# ESP8266_Encoder.net
KiCad netlist of a schematic drawn in EAGLE
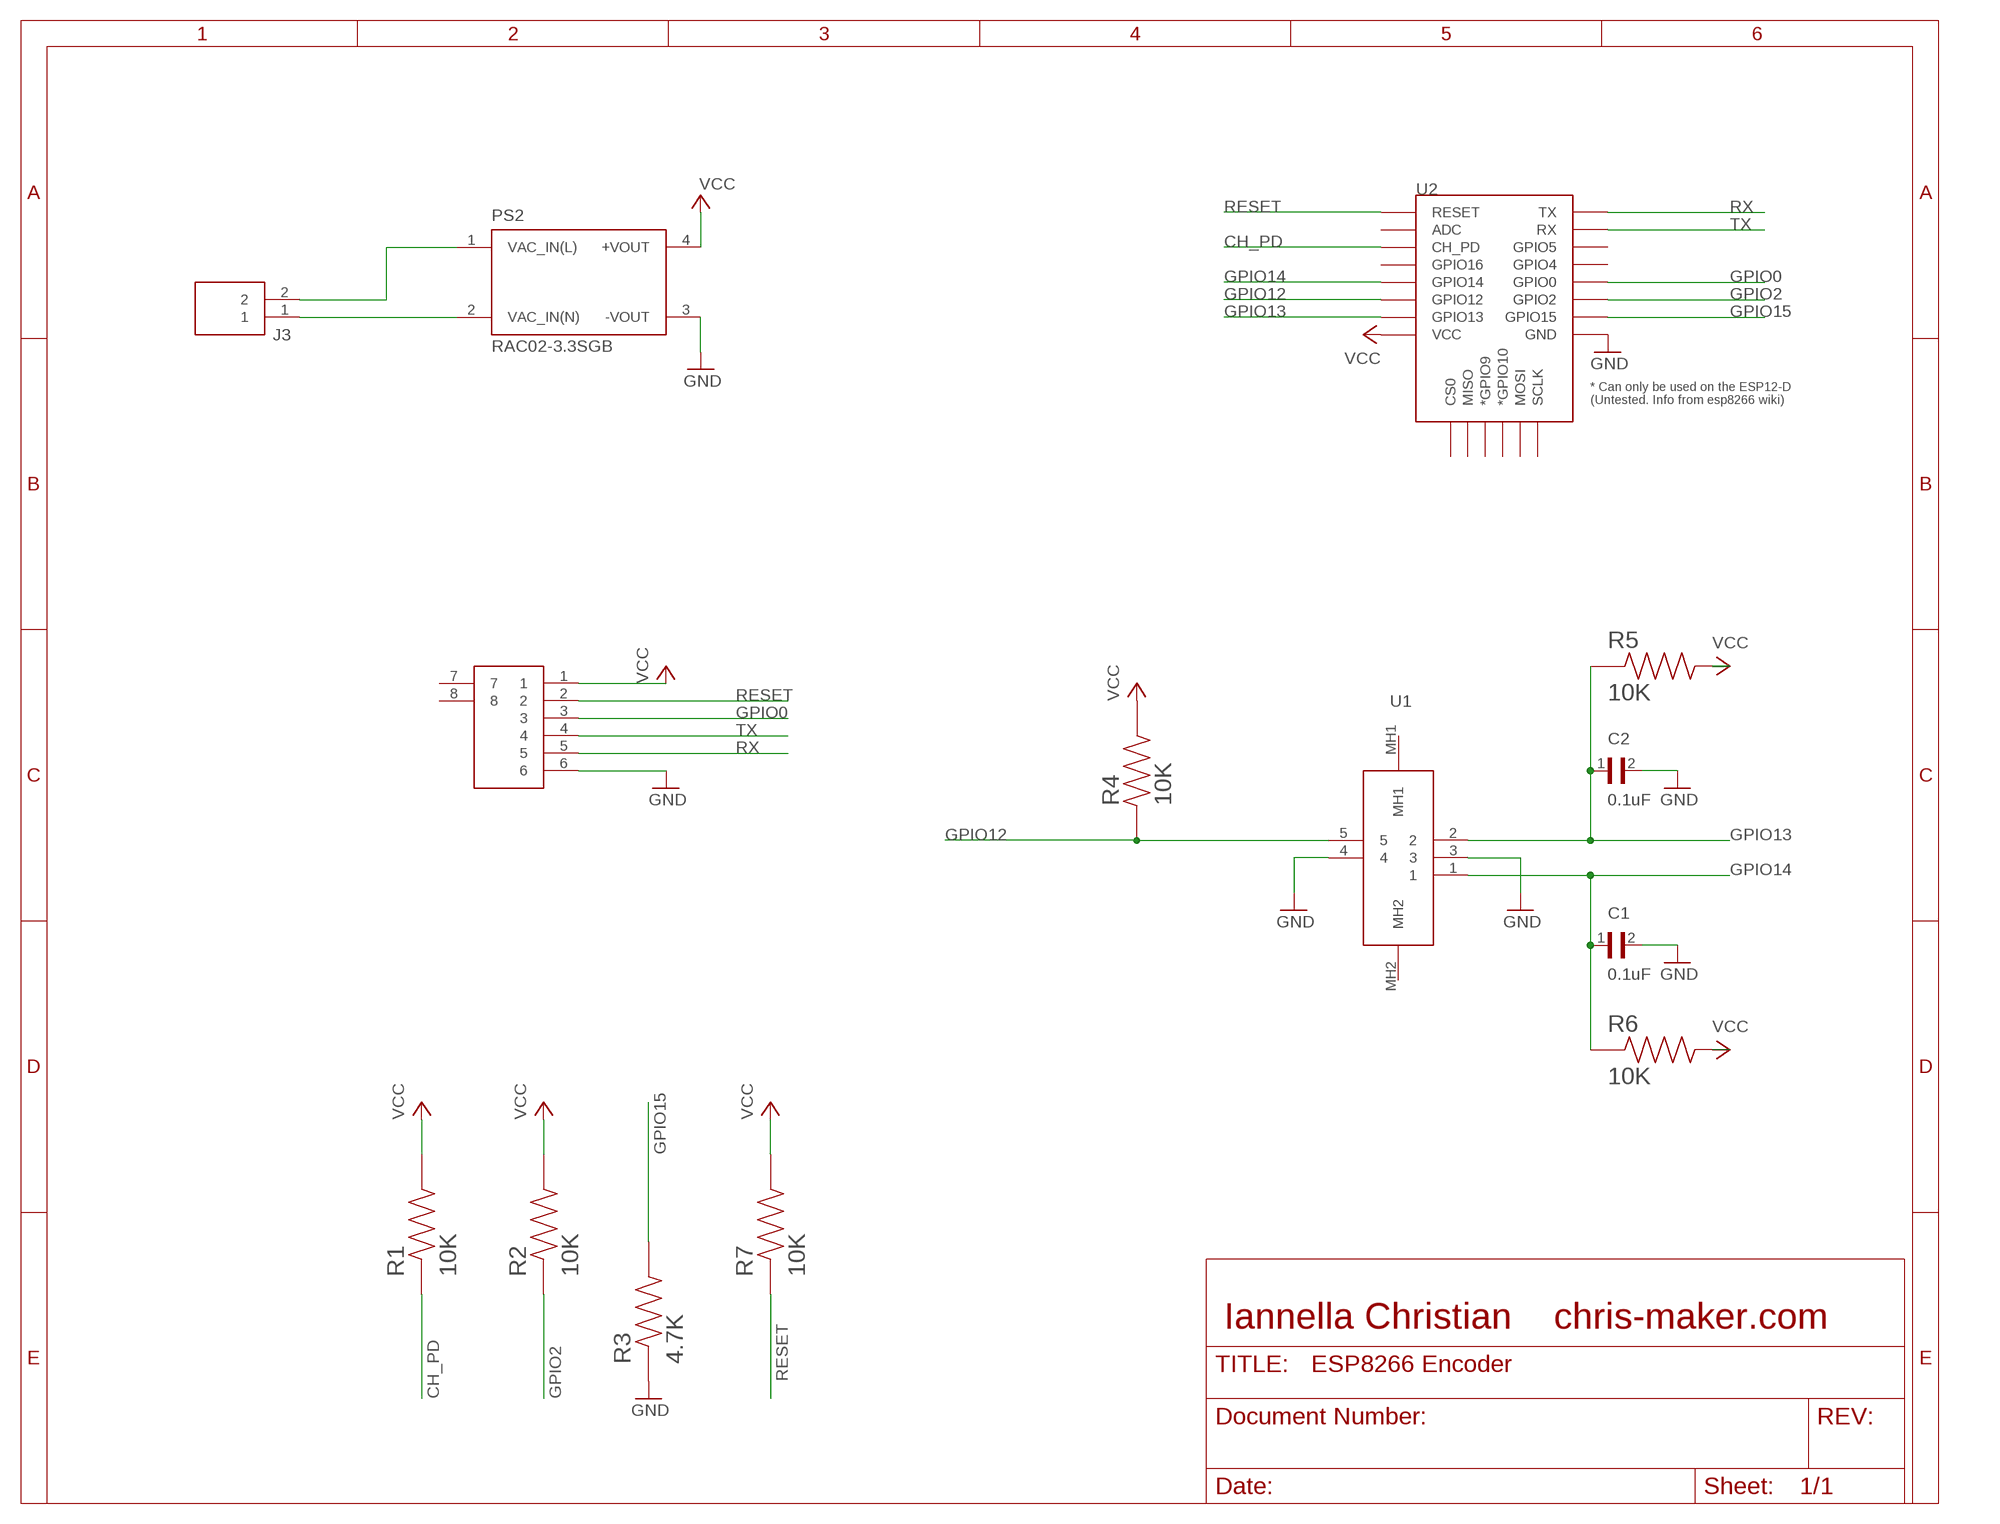
[diagram p0: schematic, sheet 1]

(export (version "E")
  (design (tool "Eeschema 10.0.6"))
  (components
    (comp (ref "C1")
      (value "0.1uF")
      (footprint "eagle-import:CAPC2012X94N")
      (fields (field (name "MF") "AVX") (field (name "MP") "0805YC103J4T2A"))
      (libsource (lib "eagle-import") (part "0805YC103J4T2A"))
    )
    (comp (ref "C2")
      (value "0.1uF")
      (footprint "eagle-import:CAPC2012X94N")
      (fields (field (name "MF") "AVX") (field (name "MP") "0805YC103J4T2A"))
      (libsource (lib "eagle-import") (part "0805YC103J4T2A"))
    )
    (comp (ref "J1")
      (value "52852-0670")
      (footprint "eagle-import:528520670")
      (fields (field (name "MOUSER_PART_NUMBER") "538-52852-0670"))
      (libsource (lib "eagle-import") (part "52852-0670"))
    )
    (comp (ref "J3")
      (value "TB004-508-02BE")
      (footprint "eagle-import:SHDR2W100P0X508_1X2_1016X1020X")
      (fields (field (name "MOUSER_PART_NUMBER") "490-TB004-508-02BE"))
      (libsource (lib "eagle-import") (part "TB004-508-02BE"))
    )
    (comp (ref "PS2")
      (value "RAC02-3.3SGB")
      (footprint "eagle-import:CONV_RAC02-3.3SGB")
      (fields (field (name "MF") "Recom Power"))
      (libsource (lib "eagle-import") (part "RAC02-3.3SGB"))
    )
    (comp (ref "R1")
      (value "10K")
      (footprint "eagle-import:RESC2012X60N")
      (fields (field (name "MF") "Yageo") (field (name "MP") "RC0805FR-07330RL"))
      (libsource (lib "eagle-import") (part "RC0805FR-07330RL"))
    )
    (comp (ref "R2")
      (value "10K")
      (footprint "eagle-import:RESC2012X60N")
      (fields (field (name "MF") "Yageo") (field (name "MP") "RC0805FR-07330RL"))
      (libsource (lib "eagle-import") (part "RC0805FR-07330RL"))
    )
    (comp (ref "R3")
      (value "4.7K")
      (footprint "eagle-import:RESC2012X60N")
      (fields (field (name "MF") "Yageo") (field (name "MP") "RC0805FR-07330RL"))
      (libsource (lib "eagle-import") (part "RC0805FR-07330RL"))
    )
    (comp (ref "R4")
      (value "10K")
      (footprint "eagle-import:RESC2012X60N")
      (fields (field (name "MF") "Yageo") (field (name "MP") "RC0805FR-07330RL"))
      (libsource (lib "eagle-import") (part "RC0805FR-07330RL"))
    )
    (comp (ref "R5")
      (value "10K")
      (footprint "eagle-import:RESC2012X60N")
      (fields (field (name "MF") "Yageo") (field (name "MP") "RC0805FR-07330RL"))
      (libsource (lib "eagle-import") (part "RC0805FR-07330RL"))
    )
    (comp (ref "R6")
      (value "10K")
      (footprint "eagle-import:RESC2012X60N")
      (fields (field (name "MF") "Yageo") (field (name "MP") "RC0805FR-07330RL"))
      (libsource (lib "eagle-import") (part "RC0805FR-07330RL"))
    )
    (comp (ref "R7")
      (value "10K")
      (footprint "eagle-import:RESC2012X60N")
      (fields (field (name "MF") "Yageo") (field (name "MP") "RC0805FR-07330RL"))
      (libsource (lib "eagle-import") (part "RC0805FR-07330RL"))
    )
    (comp (ref "U1")
      (value "ENCODER90")
      (footprint "eagle-import:EN11VSM0AF20")
      (fields (field (name "MANUFACTURER_PART_NUMBER") "EN11-VSM0AF20"))
      (libsource (lib "eagle-import") (part "ENCODER90"))
    )
    (comp (ref "U2")
      (value "ESP12ESMD")
      (footprint "eagle-import:ESP12E-SMD")
      (libsource (lib "eagle-import") (part "ESP12ESMD"))
    )
  )
  (nets
    (net (code "1") (name "/CH_PD") (class "Default")
      (node (ref "R1") (pin "1") (pinfunction "1_1") (pintype "passive"))
      (node (ref "U2") (pin "CH_PD") (pinfunction "CH_PD_CH_PD") (pintype "bidirectional"))
    )
    (net (code "2") (name "/GPIO0") (class "Default")
      (node (ref "J1") (pin "3") (pinfunction "3_3") (pintype "bidirectional"))
      (node (ref "U2") (pin "GPIO0") (pinfunction "GPIO0_GPIO0") (pintype "bidirectional"))
    )
    (net (code "3") (name "/GPIO2") (class "Default")
      (node (ref "R2") (pin "1") (pinfunction "1_1") (pintype "passive"))
      (node (ref "U2") (pin "GPIO2") (pinfunction "GPIO2_GPIO2") (pintype "bidirectional"))
    )
    (net (code "4") (name "/GPIO12") (class "Default")
      (node (ref "R4") (pin "1") (pinfunction "1_1") (pintype "passive"))
      (node (ref "U1") (pin "5") (pinfunction "5_5") (pintype "bidirectional"))
      (node (ref "U2") (pin "GPIO12") (pinfunction "GPIO12_GPIO12") (pintype "bidirectional"))
    )
    (net (code "5") (name "/GPIO13") (class "Default")
      (node (ref "C2") (pin "1") (pinfunction "1_1") (pintype "passive"))
      (node (ref "R5") (pin "1") (pinfunction "1_1") (pintype "passive"))
      (node (ref "U1") (pin "2") (pinfunction "2_2") (pintype "bidirectional"))
      (node (ref "U2") (pin "GPIO13") (pinfunction "GPIO13_GPIO13") (pintype "bidirectional"))
    )
    (net (code "6") (name "/GPIO14") (class "Default")
      (node (ref "C1") (pin "1") (pinfunction "1_1") (pintype "passive"))
      (node (ref "R6") (pin "1") (pinfunction "1_1") (pintype "passive"))
      (node (ref "U1") (pin "1") (pinfunction "1_1") (pintype "bidirectional"))
      (node (ref "U2") (pin "GPIO14") (pinfunction "GPIO14_GPIO14") (pintype "bidirectional"))
    )
    (net (code "7") (name "/GPIO15") (class "Default")
      (node (ref "R3") (pin "2") (pinfunction "2_2") (pintype "passive"))
      (node (ref "U2") (pin "GPIO15") (pinfunction "GPIO15_GPIO15") (pintype "bidirectional"))
    )
    (net (code "8") (name "/RESET") (class "Default")
      (node (ref "J1") (pin "2") (pinfunction "2_2") (pintype "bidirectional"))
      (node (ref "R7") (pin "1") (pinfunction "1_1") (pintype "passive"))
      (node (ref "U2") (pin "RESET") (pinfunction "RESET_RESET") (pintype "bidirectional"))
    )
    (net (code "9") (name "/RX") (class "Default")
      (node (ref "J1") (pin "5") (pinfunction "5_5") (pintype "bidirectional"))
      (node (ref "U2") (pin "TXD0") (pinfunction "TX_TXD0") (pintype "bidirectional"))
    )
    (net (code "10") (name "/TX") (class "Default")
      (node (ref "J1") (pin "4") (pinfunction "4_4") (pintype "bidirectional"))
      (node (ref "U2") (pin "RXD0") (pinfunction "RX_RXD0") (pintype "bidirectional"))
    )
    (net (code "11") (name "GND") (class "Default")
      (node (ref "C1") (pin "2") (pinfunction "2_2") (pintype "passive"))
      (node (ref "C2") (pin "2") (pinfunction "2_2") (pintype "passive"))
      (node (ref "J1") (pin "6") (pinfunction "6_6") (pintype "bidirectional"))
      (node (ref "PS2") (pin "3") (pinfunction "-VOUT_3") (pintype "output"))
      (node (ref "R3") (pin "1") (pinfunction "1_1") (pintype "passive"))
      (node (ref "U1") (pin "3") (pinfunction "3_3") (pintype "bidirectional"))
      (node (ref "U1") (pin "4") (pinfunction "4_4") (pintype "bidirectional"))
      (node (ref "U2") (pin "GND") (pinfunction "GND_GND") (pintype "bidirectional"))
    )
    (net (code "12") (name "Net-(PS2-VAC_IN(L))") (class "Default")
      (node (ref "J3") (pin "2") (pinfunction "2_2") (pintype "bidirectional"))
      (node (ref "PS2") (pin "1") (pinfunction "VAC_IN(L)_1") (pintype "input"))
    )
    (net (code "13") (name "Net-(PS2-VAC_IN(N))") (class "Default")
      (node (ref "J3") (pin "1") (pinfunction "1_1") (pintype "bidirectional"))
      (node (ref "PS2") (pin "2") (pinfunction "VAC_IN(N)_2") (pintype "input"))
    )
    (net (code "14") (name "VCC") (class "Default")
      (node (ref "J1") (pin "1") (pinfunction "1_1") (pintype "bidirectional"))
      (node (ref "PS2") (pin "4") (pinfunction "+VOUT_4") (pintype "output"))
      (node (ref "R1") (pin "2") (pinfunction "2_2") (pintype "passive"))
      (node (ref "R2") (pin "2") (pinfunction "2_2") (pintype "passive"))
      (node (ref "R4") (pin "2") (pinfunction "2_2") (pintype "passive"))
      (node (ref "R5") (pin "2") (pinfunction "2_2") (pintype "passive"))
      (node (ref "R6") (pin "2") (pinfunction "2_2") (pintype "passive"))
      (node (ref "R7") (pin "2") (pinfunction "2_2") (pintype "passive"))
      (node (ref "U2") (pin "VCC") (pinfunction "VCC_VCC") (pintype "bidirectional"))
    )
    (net (code "15") (name "unconnected-(J1-Pad7)") (class "Default")
      (node (ref "J1") (pin "7") (pinfunction "7_7") (pintype "bidirectional"))
    )
    (net (code "16") (name "unconnected-(J1-Pad8)") (class "Default")
      (node (ref "J1") (pin "8") (pinfunction "8_8") (pintype "bidirectional"))
    )
    (net (code "17") (name "unconnected-(U1-PadMH1)") (class "Default")
      (node (ref "U1") (pin "MH1") (pinfunction "MH1_MH1") (pintype "bidirectional"))
    )
    (net (code "18") (name "unconnected-(U1-PadMH2)") (class "Default")
      (node (ref "U1") (pin "MH2") (pinfunction "MH2_MH2") (pintype "bidirectional"))
    )
    (net (code "19") (name "unconnected-(U2-*GPIO9-PadGPIO9)") (class "Default")
      (node (ref "U2") (pin "GPIO9") (pinfunction "*GPIO9_GPIO9") (pintype "bidirectional"))
    )
    (net (code "20") (name "unconnected-(U2-*GPIO10-PadGPIO10)") (class "Default")
      (node (ref "U2") (pin "GPIO10") (pinfunction "*GPIO10_GPIO10") (pintype "bidirectional"))
    )
    (net (code "21") (name "unconnected-(U2-PadADC)") (class "Default")
      (node (ref "U2") (pin "ADC") (pinfunction "ADC_ADC") (pintype "bidirectional"))
    )
    (net (code "22") (name "unconnected-(U2-PadCS0)") (class "Default")
      (node (ref "U2") (pin "CS0") (pinfunction "CS0_CS0") (pintype "bidirectional"))
    )
    (net (code "23") (name "unconnected-(U2-PadGPIO4)") (class "Default")
      (node (ref "U2") (pin "GPIO4") (pinfunction "GPIO4_GPIO4") (pintype "bidirectional"))
    )
    (net (code "24") (name "unconnected-(U2-PadGPIO5)") (class "Default")
      (node (ref "U2") (pin "GPIO5") (pinfunction "GPIO5_GPIO5") (pintype "bidirectional"))
    )
    (net (code "25") (name "unconnected-(U2-PadGPIO16)") (class "Default")
      (node (ref "U2") (pin "GPIO16") (pinfunction "GPIO16_GPIO16") (pintype "bidirectional"))
    )
    (net (code "26") (name "unconnected-(U2-PadMISO)") (class "Default")
      (node (ref "U2") (pin "MISO") (pinfunction "MISO_MISO") (pintype "bidirectional"))
    )
    (net (code "27") (name "unconnected-(U2-PadMOSI)") (class "Default")
      (node (ref "U2") (pin "MOSI") (pinfunction "MOSI_MOSI") (pintype "bidirectional"))
    )
    (net (code "28") (name "unconnected-(U2-PadSCLK)") (class "Default")
      (node (ref "U2") (pin "SCLK") (pinfunction "SCLK_SCLK") (pintype "bidirectional"))
    )
  )
)
